# 2HP2CV.net
KiCad netlist of a schematic drawn in EAGLE
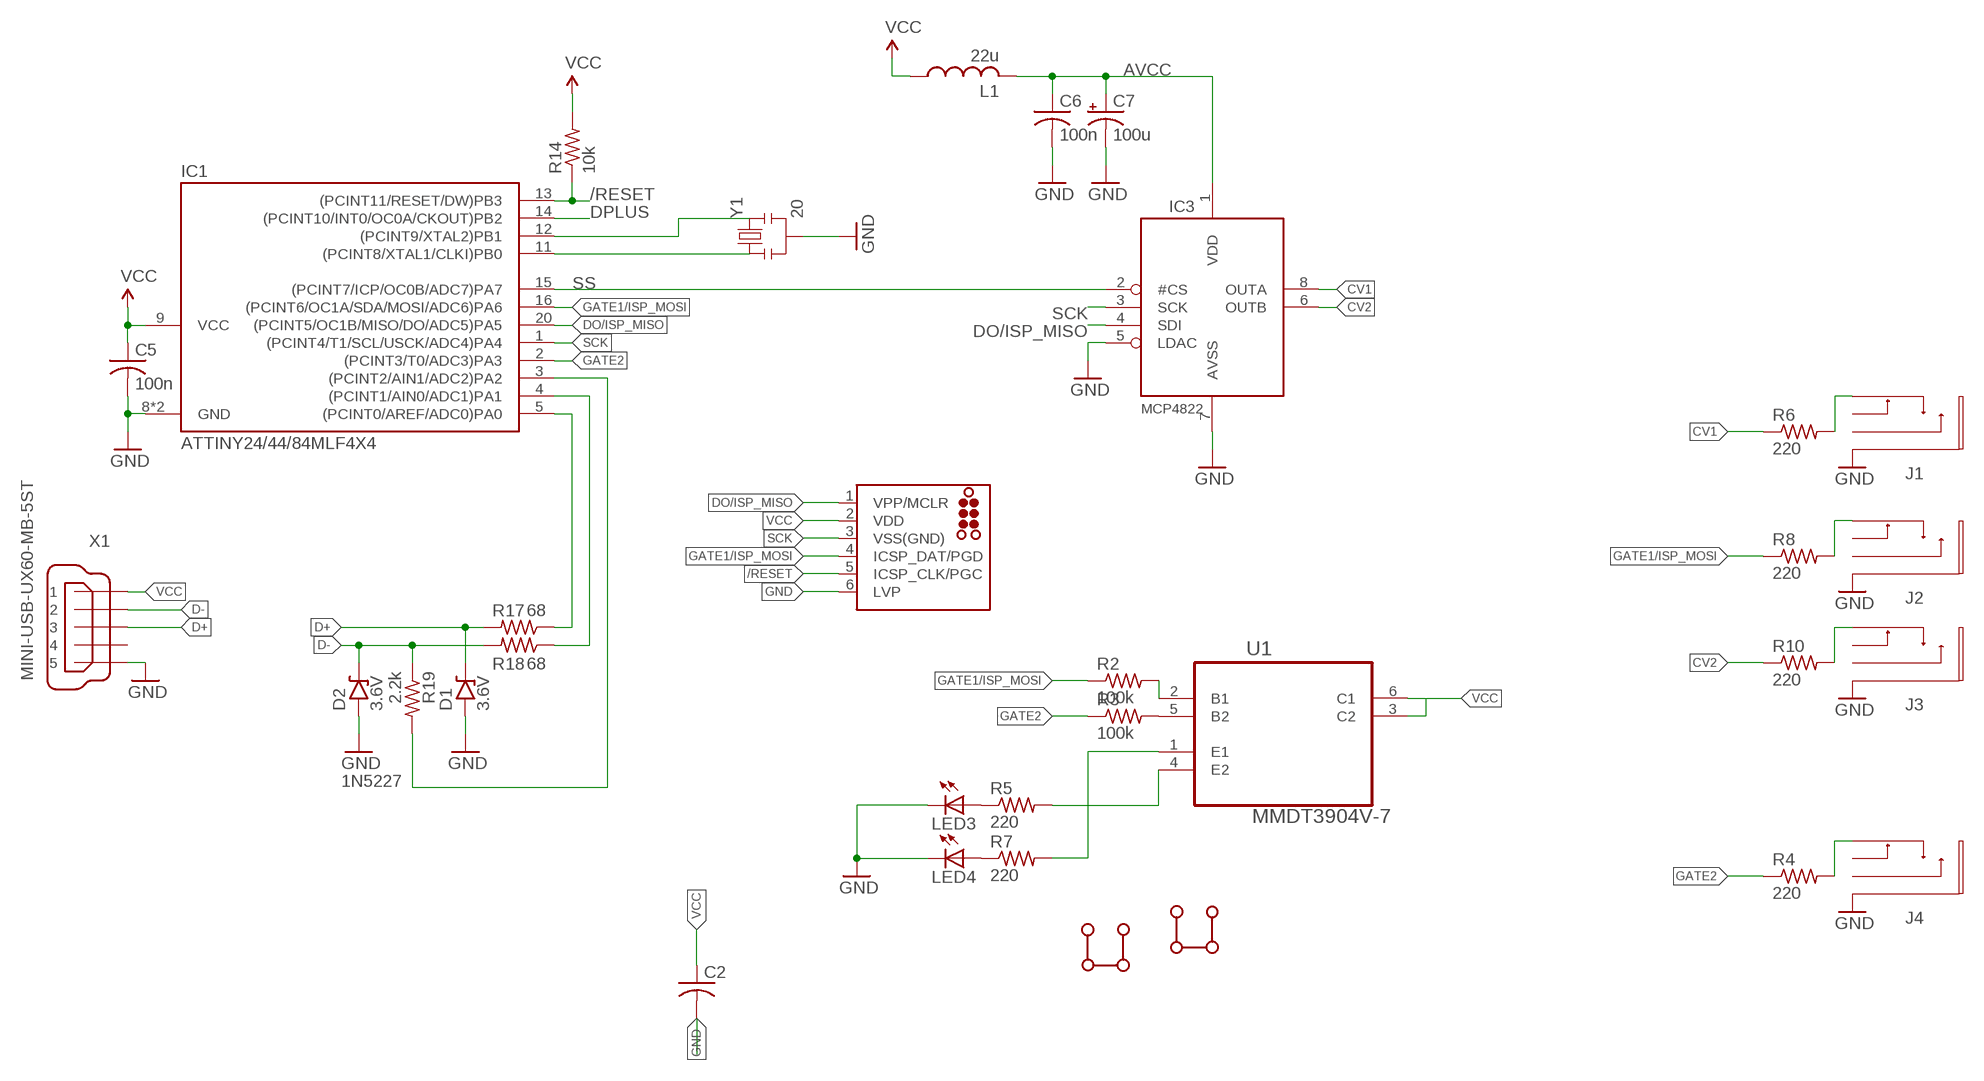
[diagram p0: schematic, sheet 1]

(export (version "E")
  (design (tool "Eeschema 10.0.6"))
  (components
    (comp (ref "C2")
      (value "C-USC0805K")
      (footprint "eagle-import:C0805K")
      (libsource (lib "eagle-import") (part "C-USC0805K"))
    )
    (comp (ref "C5")
      (value "100n")
      (footprint "eagle-import:C0402")
      (libsource (lib "eagle-import") (part "C-USC0402"))
    )
    (comp (ref "C6")
      (value "100n")
      (footprint "eagle-import:C0402")
      (libsource (lib "eagle-import") (part "C-USC0402"))
    )
    (comp (ref "C7")
      (value "100u")
      (footprint "eagle-import:A_3216-18R")
      (libsource (lib "eagle-import") (part "CPOL-USA/3216-18R"))
    )
    (comp (ref "D1")
      (value "3.6V")
      (footprint "eagle-import:SOD323-R")
      (libsource (lib "eagle-import") (part "1N47XXSOD323R"))
    )
    (comp (ref "D2")
      (value "3.6V")
      (footprint "eagle-import:SOD323-R")
      (libsource (lib "eagle-import") (part "1N47XXSOD323R"))
    )
    (comp (ref "IC1")
      (value "ATTINY24/44/84MLF4X4")
      (footprint "eagle-import:MLF20-4X4")
      (libsource (lib "eagle-import") (part "ATTINY24/44/84MLF4X4"))
    )
    (comp (ref "IC3")
      (value "MCP4822SO08")
      (footprint "eagle-import:SO08")
      (libsource (lib "eagle-import") (part "MCP4822SO08"))
    )
    (comp (ref "J1")
      (value "PJ327E")
      (footprint "eagle-import:PJ327")
      (libsource (lib "eagle-import") (part "PJ327E"))
    )
    (comp (ref "J2")
      (value "PJ327E")
      (footprint "eagle-import:PJ327")
      (libsource (lib "eagle-import") (part "PJ327E"))
    )
    (comp (ref "J3")
      (value "PJ327E")
      (footprint "eagle-import:PJ327")
      (libsource (lib "eagle-import") (part "PJ327E"))
    )
    (comp (ref "J4")
      (value "PJ327E")
      (footprint "eagle-import:PJ327")
      (libsource (lib "eagle-import") (part "PJ327E"))
    )
    (comp (ref "J5")
      (value "TC2030-MCP-NL")
      (footprint "eagle-import:TC2030-MCP-NL")
      (libsource (lib "eagle-import") (part "TC2030-MCP-NL"))
    )
    (comp (ref "L1")
      (value "22u")
      (footprint "eagle-import:L2012C")
      (libsource (lib "eagle-import") (part "L-USL2012C"))
    )
    (comp (ref "LED3")
      (value "LED3MM")
      (footprint "eagle-import:LED3MM")
      (libsource (lib "eagle-import") (part "LED3MM"))
    )
    (comp (ref "LED4")
      (value "LED3MM")
      (footprint "eagle-import:LED3MM")
      (libsource (lib "eagle-import") (part "LED3MM"))
    )
    (comp (ref "R2")
      (value "100k")
      (footprint "eagle-import:R0402")
      (libsource (lib "eagle-import") (part "R-US_R0402"))
    )
    (comp (ref "R3")
      (value "100k")
      (footprint "eagle-import:R0402")
      (libsource (lib "eagle-import") (part "R-US_R0402"))
    )
    (comp (ref "R4")
      (value "220")
      (footprint "eagle-import:R0402")
      (libsource (lib "eagle-import") (part "R-US_R0402"))
    )
    (comp (ref "R5")
      (value "220")
      (footprint "eagle-import:R0402")
      (libsource (lib "eagle-import") (part "R-US_R0402"))
    )
    (comp (ref "R6")
      (value "220")
      (footprint "eagle-import:R0402")
      (libsource (lib "eagle-import") (part "R-US_R0402"))
    )
    (comp (ref "R7")
      (value "220")
      (footprint "eagle-import:R0402")
      (libsource (lib "eagle-import") (part "R-US_R0402"))
    )
    (comp (ref "R8")
      (value "220")
      (footprint "eagle-import:R0402")
      (libsource (lib "eagle-import") (part "R-US_R0402"))
    )
    (comp (ref "R10")
      (value "220")
      (footprint "eagle-import:R0402")
      (libsource (lib "eagle-import") (part "R-US_R0402"))
    )
    (comp (ref "R14")
      (value "10k")
      (footprint "eagle-import:R0402")
      (libsource (lib "eagle-import") (part "resistor_R-US_R0402"))
    )
    (comp (ref "R17")
      (value "68")
      (footprint "eagle-import:R0402")
      (libsource (lib "eagle-import") (part "resistor_R-US_R0402"))
    )
    (comp (ref "R18")
      (value "68")
      (footprint "eagle-import:R0402")
      (libsource (lib "eagle-import") (part "resistor_R-US_R0402"))
    )
    (comp (ref "R19")
      (value "2.2k")
      (footprint "eagle-import:R0402")
      (libsource (lib "eagle-import") (part "resistor_R-US_R0402"))
    )
    (comp (ref "U$5")
      (value "PCB-69M3")
      (footprint "eagle-import:PCB-69M3")
      (libsource (lib "eagle-import") (part "PCB-69M3"))
    )
    (comp (ref "U$6")
      (value "PCB-69M3")
      (footprint "eagle-import:PCB-69M3")
      (libsource (lib "eagle-import") (part "PCB-69M3"))
    )
    (comp (ref "U1")
      (value "MMDT3904V-7")
      (footprint "eagle-import:SOT50P170X60-6N")
      (libsource (lib "eagle-import") (part "MMDT3904V-7"))
    )
    (comp (ref "X1")
      (value "MINI-USB-UX60-MB-5ST")
      (footprint "eagle-import:UX60-MB-5ST")
      (libsource (lib "eagle-import") (part "MINI-USB-UX60-MB-5ST"))
    )
    (comp (ref "Y1")
      (value "20")
      (footprint "eagle-import:RESONATOR-SMD")
      (libsource (lib "eagle-import") (part "RESONATOR16MHZ"))
    )
  )
  (nets
    (net (code "1") (name "AVCC") (class "Default")
      (node (ref "C6") (pin "1") (pinfunction "1_1") (pintype "passive"))
      (node (ref "C7") (pin "+") (pinfunction "+_+") (pintype "passive"))
      (node (ref "IC3") (pin "1") (pinfunction "VDD_1") (pintype "power_in"))
      (node (ref "L1") (pin "2") (pinfunction "2_2") (pintype "passive"))
    )
    (net (code "2") (name "CV1") (class "Default")
      (node (ref "IC3") (pin "8") (pinfunction "OUTA_8") (pintype "output"))
      (node (ref "R6") (pin "1") (pinfunction "1_1") (pintype "passive"))
    )
    (net (code "3") (name "CV2") (class "Default")
      (node (ref "IC3") (pin "6") (pinfunction "OUTB_6") (pintype "output"))
      (node (ref "R10") (pin "1") (pinfunction "1_1") (pintype "passive"))
    )
    (net (code "4") (name "D+") (class "Default")
      (node (ref "D1") (pin "C") (pinfunction "C_C") (pintype "passive"))
      (node (ref "R17") (pin "2") (pinfunction "2_2") (pintype "passive"))
      (node (ref "X1") (pin "3") (pinfunction "3_3") (pintype "input"))
    )
    (net (code "5") (name "D-") (class "Default")
      (node (ref "D2") (pin "C") (pinfunction "C_C") (pintype "passive"))
      (node (ref "R18") (pin "2") (pinfunction "2_2") (pintype "passive"))
      (node (ref "R19") (pin "1") (pinfunction "1_1") (pintype "passive"))
      (node (ref "X1") (pin "2") (pinfunction "2_2") (pintype "input"))
    )
    (net (code "6") (name "DO{slash}ISP_MISO") (class "Default")
      (node (ref "IC1") (pin "20") (pinfunction "(PCINT5/OC1B/MISO/DO/ADC5)PA5_20") (pintype "bidirectional"))
      (node (ref "IC3") (pin "4") (pinfunction "SDI_4") (pintype "input"))
      (node (ref "J5") (pin "1") (pinfunction "VPP/MCLR_1") (pintype "passive"))
    )
    (net (code "7") (name "DPLUS") (class "Default")
      (node (ref "IC1") (pin "14") (pinfunction "(PCINT10/INT0/OC0A/CKOUT)PB2_14") (pintype "bidirectional"))
      (node (ref "IC1") (pin "5") (pinfunction "(PCINT0/AREF/ADC0)PA0_5") (pintype "bidirectional"))
      (node (ref "R17") (pin "1") (pinfunction "1_1") (pintype "passive"))
    )
    (net (code "8") (name "GATE1{slash}ISP_MOSI") (class "Default")
      (node (ref "IC1") (pin "16") (pinfunction "(PCINT6/OC1A/SDA/MOSI/ADC6)PA6_16") (pintype "bidirectional"))
      (node (ref "J5") (pin "4") (pinfunction "ICSP_DAT/PGD_4") (pintype "bidirectional"))
      (node (ref "R2") (pin "1") (pinfunction "1_1") (pintype "passive"))
      (node (ref "R8") (pin "1") (pinfunction "1_1") (pintype "passive"))
    )
    (net (code "9") (name "GATE2") (class "Default")
      (node (ref "IC1") (pin "2") (pinfunction "(PCINT3/T0/ADC3)PA3_2") (pintype "bidirectional"))
      (node (ref "R3") (pin "1") (pinfunction "1_1") (pintype "passive"))
      (node (ref "R4") (pin "1") (pinfunction "1_1") (pintype "passive"))
    )
    (net (code "10") (name "GND") (class "Default")
      (node (ref "C2") (pin "2") (pinfunction "2_2") (pintype "passive"))
      (node (ref "C5") (pin "2") (pinfunction "2_2") (pintype "passive"))
      (node (ref "C6") (pin "2") (pinfunction "2_2") (pintype "passive"))
      (node (ref "C7") (pin "-") (pinfunction "-_-") (pintype "passive"))
      (node (ref "D1") (pin "A") (pinfunction "A_A") (pintype "passive"))
      (node (ref "D2") (pin "A") (pinfunction "A_A") (pintype "passive"))
      (node (ref "IC1") (pin "8") (pinfunction "GND_8") (pintype "power_in"))
      (node (ref "IC1") (pin "TH") (pinfunction "GND_TH") (pintype "power_in"))
      (node (ref "IC3") (pin "5") (pinfunction "LDAC_5") (pintype "input"))
      (node (ref "IC3") (pin "7") (pinfunction "AVSS_7") (pintype "power_in"))
      (node (ref "J1") (pin "P$1") (pinfunction "P$1_P$1") (pintype "bidirectional"))
      (node (ref "J2") (pin "P$1") (pinfunction "P$1_P$1") (pintype "bidirectional"))
      (node (ref "J3") (pin "P$1") (pinfunction "P$1_P$1") (pintype "bidirectional"))
      (node (ref "J4") (pin "P$1") (pinfunction "P$1_P$1") (pintype "bidirectional"))
      (node (ref "J5") (pin "6") (pinfunction "LVP_6") (pintype "bidirectional"))
      (node (ref "LED3") (pin "K") (pinfunction "C_K") (pintype "passive"))
      (node (ref "LED4") (pin "K") (pinfunction "C_K") (pintype "passive"))
      (node (ref "X1") (pin "5") (pinfunction "5_5") (pintype "input"))
      (node (ref "Y1") (pin "2") (pinfunction "2_2") (pintype "passive"))
    )
    (net (code "11") (name "Net-(IC1-(PCINT1{slash}AIN0{slash}ADC1)PA1)") (class "Default")
      (node (ref "IC1") (pin "4") (pinfunction "(PCINT1/AIN0/ADC1)PA1_4") (pintype "bidirectional"))
      (node (ref "R18") (pin "1") (pinfunction "1_1") (pintype "passive"))
    )
    (net (code "12") (name "Net-(IC1-(PCINT2{slash}AIN1{slash}ADC2)PA2)") (class "Default")
      (node (ref "IC1") (pin "3") (pinfunction "(PCINT2/AIN1/ADC2)PA2_3") (pintype "bidirectional"))
      (node (ref "R19") (pin "2") (pinfunction "2_2") (pintype "passive"))
    )
    (net (code "13") (name "Net-(IC1-(PCINT8{slash}XTAL1{slash}CLKI)PB0)") (class "Default")
      (node (ref "IC1") (pin "11") (pinfunction "(PCINT8/XTAL1/CLKI)PB0_11") (pintype "bidirectional"))
      (node (ref "Y1") (pin "1") (pinfunction "1_1") (pintype "passive"))
    )
    (net (code "14") (name "Net-(IC1-(PCINT9{slash}XTAL2)PB1)") (class "Default")
      (node (ref "IC1") (pin "12") (pinfunction "(PCINT9/XTAL2)PB1_12") (pintype "bidirectional"))
      (node (ref "Y1") (pin "3") (pinfunction "3_3") (pintype "passive"))
    )
    (net (code "15") (name "Net-(J1-PadP$2)") (class "Default")
      (node (ref "J1") (pin "P$2") (pinfunction "P$2_P$2") (pintype "bidirectional"))
      (node (ref "R6") (pin "2") (pinfunction "2_2") (pintype "passive"))
    )
    (net (code "16") (name "Net-(J2-PadP$2)") (class "Default")
      (node (ref "J2") (pin "P$2") (pinfunction "P$2_P$2") (pintype "bidirectional"))
      (node (ref "R8") (pin "2") (pinfunction "2_2") (pintype "passive"))
    )
    (net (code "17") (name "Net-(J3-PadP$2)") (class "Default")
      (node (ref "J3") (pin "P$2") (pinfunction "P$2_P$2") (pintype "bidirectional"))
      (node (ref "R10") (pin "2") (pinfunction "2_2") (pintype "passive"))
    )
    (net (code "18") (name "Net-(J4-PadP$2)") (class "Default")
      (node (ref "J4") (pin "P$2") (pinfunction "P$2_P$2") (pintype "bidirectional"))
      (node (ref "R4") (pin "2") (pinfunction "2_2") (pintype "passive"))
    )
    (net (code "19") (name "Net-(LED3-PadA)") (class "Default")
      (node (ref "LED3") (pin "A") (pinfunction "A_A") (pintype "passive"))
      (node (ref "R5") (pin "1") (pinfunction "1_1") (pintype "passive"))
    )
    (net (code "20") (name "Net-(LED4-PadA)") (class "Default")
      (node (ref "LED4") (pin "A") (pinfunction "A_A") (pintype "passive"))
      (node (ref "R7") (pin "1") (pinfunction "1_1") (pintype "passive"))
    )
    (net (code "21") (name "Net-(U1-B1)") (class "Default")
      (node (ref "R2") (pin "2") (pinfunction "2_2") (pintype "passive"))
      (node (ref "U1") (pin "2") (pinfunction "B1_2") (pintype "passive"))
    )
    (net (code "22") (name "Net-(U1-B2)") (class "Default")
      (node (ref "R3") (pin "2") (pinfunction "2_2") (pintype "passive"))
      (node (ref "U1") (pin "5") (pinfunction "B2_5") (pintype "passive"))
    )
    (net (code "23") (name "Net-(U1-E1)") (class "Default")
      (node (ref "R7") (pin "2") (pinfunction "2_2") (pintype "passive"))
      (node (ref "U1") (pin "1") (pinfunction "E1_1") (pintype "passive"))
    )
    (net (code "24") (name "Net-(U1-E2)") (class "Default")
      (node (ref "R5") (pin "2") (pinfunction "2_2") (pintype "passive"))
      (node (ref "U1") (pin "4") (pinfunction "E2_4") (pintype "passive"))
    )
    (net (code "25") (name "SCK") (class "Default")
      (node (ref "IC1") (pin "1") (pinfunction "(PCINT4/T1/SCL/USCK/ADC4)PA4_1") (pintype "bidirectional"))
      (node (ref "IC3") (pin "3") (pinfunction "SCK_3") (pintype "input"))
      (node (ref "J5") (pin "3") (pinfunction "VSS(GND)_3") (pintype "power_in"))
    )
    (net (code "26") (name "SS") (class "Default")
      (node (ref "IC1") (pin "15") (pinfunction "(PCINT7/ICP/OC0B/ADC7)PA7_15") (pintype "bidirectional"))
      (node (ref "IC3") (pin "2") (pinfunction "#CS_2") (pintype "input"))
    )
    (net (code "27") (name "VCC") (class "Default")
      (node (ref "C2") (pin "1") (pinfunction "1_1") (pintype "passive"))
      (node (ref "C5") (pin "1") (pinfunction "1_1") (pintype "passive"))
      (node (ref "IC1") (pin "9") (pinfunction "VCC_9") (pintype "power_in"))
      (node (ref "J5") (pin "2") (pinfunction "VDD_2") (pintype "power_in"))
      (node (ref "L1") (pin "1") (pinfunction "1_1") (pintype "passive"))
      (node (ref "R14") (pin "2") (pinfunction "2_2") (pintype "passive"))
      (node (ref "U1") (pin "3") (pinfunction "C2_3") (pintype "passive"))
      (node (ref "U1") (pin "6") (pinfunction "C1_6") (pintype "passive"))
      (node (ref "X1") (pin "1") (pinfunction "1_1") (pintype "input"))
    )
    (net (code "28") (name "unconnected-(J1-PadP$3)") (class "Default")
      (node (ref "J1") (pin "P$3") (pinfunction "P$3_P$3") (pintype "bidirectional"))
    )
    (net (code "29") (name "unconnected-(J1-PadP$5)") (class "Default")
      (node (ref "J1") (pin "P$5") (pinfunction "P$5_P$5") (pintype "bidirectional"))
    )
    (net (code "30") (name "unconnected-(J2-PadP$3)") (class "Default")
      (node (ref "J2") (pin "P$3") (pinfunction "P$3_P$3") (pintype "bidirectional"))
    )
    (net (code "31") (name "unconnected-(J2-PadP$5)") (class "Default")
      (node (ref "J2") (pin "P$5") (pinfunction "P$5_P$5") (pintype "bidirectional"))
    )
    (net (code "32") (name "unconnected-(J3-PadP$3)") (class "Default")
      (node (ref "J3") (pin "P$3") (pinfunction "P$3_P$3") (pintype "bidirectional"))
    )
    (net (code "33") (name "unconnected-(J3-PadP$5)") (class "Default")
      (node (ref "J3") (pin "P$5") (pinfunction "P$5_P$5") (pintype "bidirectional"))
    )
    (net (code "34") (name "unconnected-(J4-PadP$3)") (class "Default")
      (node (ref "J4") (pin "P$3") (pinfunction "P$3_P$3") (pintype "bidirectional"))
    )
    (net (code "35") (name "unconnected-(J4-PadP$5)") (class "Default")
      (node (ref "J4") (pin "P$5") (pinfunction "P$5_P$5") (pintype "bidirectional"))
    )
    (net (code "36") (name "unconnected-(U$5-PadP$1)") (class "Default")
      (node (ref "U$5") (pin "P$1") (pinfunction "P$1_P$1") (pintype "input"))
    )
    (net (code "37") (name "unconnected-(U$5-PadP$2)") (class "Default")
      (node (ref "U$5") (pin "P$2") (pinfunction "P$2_P$2") (pintype "input"))
    )
    (net (code "38") (name "unconnected-(U$5-PadP$3)") (class "Default")
      (node (ref "U$5") (pin "P$3") (pinfunction "P$3_P$3") (pintype "input"))
    )
    (net (code "39") (name "unconnected-(U$5-PadP$4)") (class "Default")
      (node (ref "U$5") (pin "P$4") (pinfunction "P$4_P$4") (pintype "input"))
    )
    (net (code "40") (name "unconnected-(U$6-PadP$1)") (class "Default")
      (node (ref "U$6") (pin "P$1") (pinfunction "P$1_P$1") (pintype "input"))
    )
    (net (code "41") (name "unconnected-(U$6-PadP$2)") (class "Default")
      (node (ref "U$6") (pin "P$2") (pinfunction "P$2_P$2") (pintype "input"))
    )
    (net (code "42") (name "unconnected-(U$6-PadP$3)") (class "Default")
      (node (ref "U$6") (pin "P$3") (pinfunction "P$3_P$3") (pintype "input"))
    )
    (net (code "43") (name "unconnected-(U$6-PadP$4)") (class "Default")
      (node (ref "U$6") (pin "P$4") (pinfunction "P$4_P$4") (pintype "input"))
    )
    (net (code "44") (name "unconnected-(X1-Pad4)") (class "Default")
      (node (ref "X1") (pin "4") (pinfunction "4_4") (pintype "input"))
    )
    (net (code "45") (name "{slash}RESET") (class "Default")
      (node (ref "IC1") (pin "13") (pinfunction "(PCINT11/RESET/DW)PB3_13") (pintype "bidirectional"))
      (node (ref "J5") (pin "5") (pinfunction "ICSP_CLK/PGC_5") (pintype "output"))
      (node (ref "R14") (pin "1") (pinfunction "1_1") (pintype "passive"))
    )
  )
)
